# I2C-RTC.net
KiCad netlist of a schematic drawn in Altium Designer
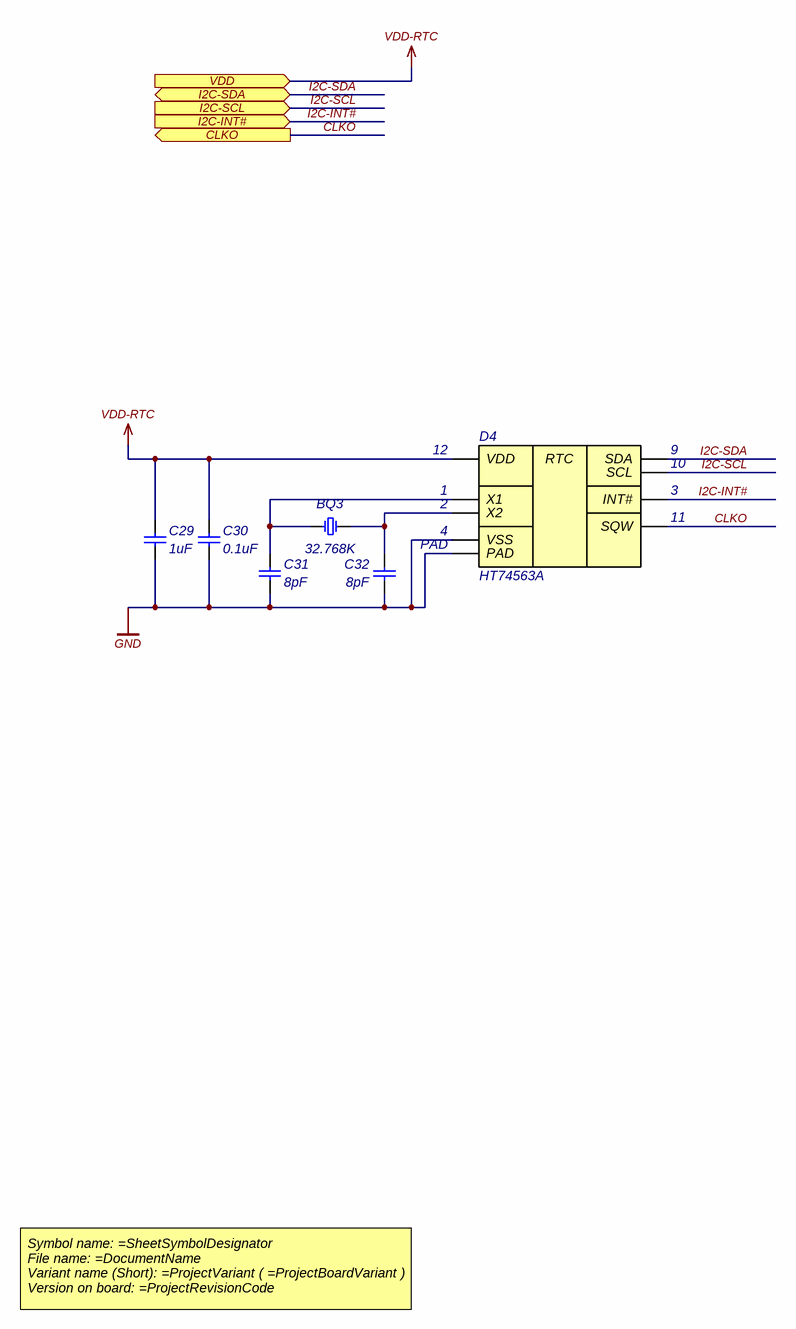
[diagram p0: I2C-RTC.SchDoc]

(export (version "E")
  (design (tool "Eeschema 10.0.6"))
  (components
    (comp (ref "BQ3")
      (value "32.768K")
      (footprint "SMD1610-2")
      (description "32.768kHz 12.5pF ±20ppm SMD1610-2PCrystal")
      (fields (field (name "PART NUMBER") "SMD1610-32.768K-12.5pF-20ppm") (field (name "TOLERANCE") "20ppm"))
      (libsource (lib "ATB") (part "BQ"))
    )
    (comp (ref "C29")
      (value "1uF")
      (footprint "C0402")
      (fields
        (field (name "PART NUMBER") "0402-X5R-10V-1uF±10%")
        (field (name "VOLTAGE") "10V")
        (field (name "TOLERANCE") "10%")
      )
      (libsource (lib "ATB") (part "C"))
    )
    (comp (ref "C30")
      (value "0.1uF")
      (footprint "C0402")
      (fields
        (field (name "PART NUMBER") "0402-X7R-16V-0.1uF±10%")
        (field (name "VOLTAGE") "16V")
        (field (name "TOLERANCE") "10%")
      )
      (libsource (lib "ATB") (part "C"))
    )
    (comp (ref "C31")
      (value "8pF")
      (footprint "C0402")
      (fields
        (field (name "PART NUMBER") "0402-NP0-50V-8pF±0.25pF")
        (field (name "VOLTAGE") "50V")
        (field (name "TOLERANCE") "0.25pF")
      )
      (libsource (lib "ATB") (part "C"))
    )
    (comp (ref "C32")
      (value "8pF")
      (footprint "C0402")
      (fields
        (field (name "PART NUMBER") "0402-NP0-50V-8pF±0.25pF")
        (field (name "VOLTAGE") "50V")
        (field (name "TOLERANCE") "0.25pF")
      )
      (libsource (lib "ATB") (part "C"))
    )
    (comp (ref "D4")
      (value "HT74563A")
      (footprint "QFN16-3X3P0.5-4X4PAD")
      (description "RTC Clock QFN-16")
      (fields (field (name "MANUFACTURER") "HTCSEMI"))
      (libsource (lib "ATB") (part "HT74563A"))
    )
  )
  (nets
    (net (code "1") (name "/CLKO") (class "Default")
      (node (ref "D4") (pin "11") (pinfunction "SQW_11") (pintype "passive"))
    )
    (net (code "2") (name "/I2C-INT#") (class "Default")
      (node (ref "D4") (pin "3") (pinfunction "INT#_3") (pintype "passive"))
    )
    (net (code "3") (name "/I2C-SCL") (class "Default")
      (node (ref "D4") (pin "10") (pinfunction "SCL_10") (pintype "passive"))
    )
    (net (code "4") (name "/I2C-SDA") (class "Default")
      (node (ref "D4") (pin "9") (pinfunction "SDA_9") (pintype "passive"))
    )
    (net (code "5") (name "GND") (class "Default")
      (node (ref "C29") (pin "2") (pinfunction "2_2") (pintype "passive"))
      (node (ref "C30") (pin "2") (pinfunction "2_2") (pintype "passive"))
      (node (ref "C31") (pin "2") (pinfunction "2_2") (pintype "passive"))
      (node (ref "C32") (pin "2") (pinfunction "2_2") (pintype "passive"))
      (node (ref "D4") (pin "4") (pinfunction "VSS_4") (pintype "passive"))
      (node (ref "D4") (pin "PAD") (pinfunction "PAD_PAD") (pintype "passive"))
    )
    (net (code "6") (name "Net-(BQ3-inp)") (class "Default")
      (node (ref "BQ3") (pin "1") (pinfunction "inp_1") (pintype "passive"))
      (node (ref "C31") (pin "1") (pinfunction "1_1") (pintype "passive"))
      (node (ref "D4") (pin "1") (pinfunction "X1_1") (pintype "passive"))
    )
    (net (code "7") (name "Net-(BQ3-out)") (class "Default")
      (node (ref "BQ3") (pin "2") (pinfunction "out_2") (pintype "passive"))
      (node (ref "C32") (pin "1") (pinfunction "1_1") (pintype "passive"))
      (node (ref "D4") (pin "2") (pinfunction "X2_2") (pintype "passive"))
    )
    (net (code "8") (name "VDD-RTC") (class "Default")
      (node (ref "C29") (pin "1") (pinfunction "1_1") (pintype "passive"))
      (node (ref "C30") (pin "1") (pinfunction "1_1") (pintype "passive"))
      (node (ref "D4") (pin "12") (pinfunction "VDD_12") (pintype "passive"))
    )
  )
)
